# USB_OTG_HS.net
KiCad netlist of a schematic drawn in Altium Designer
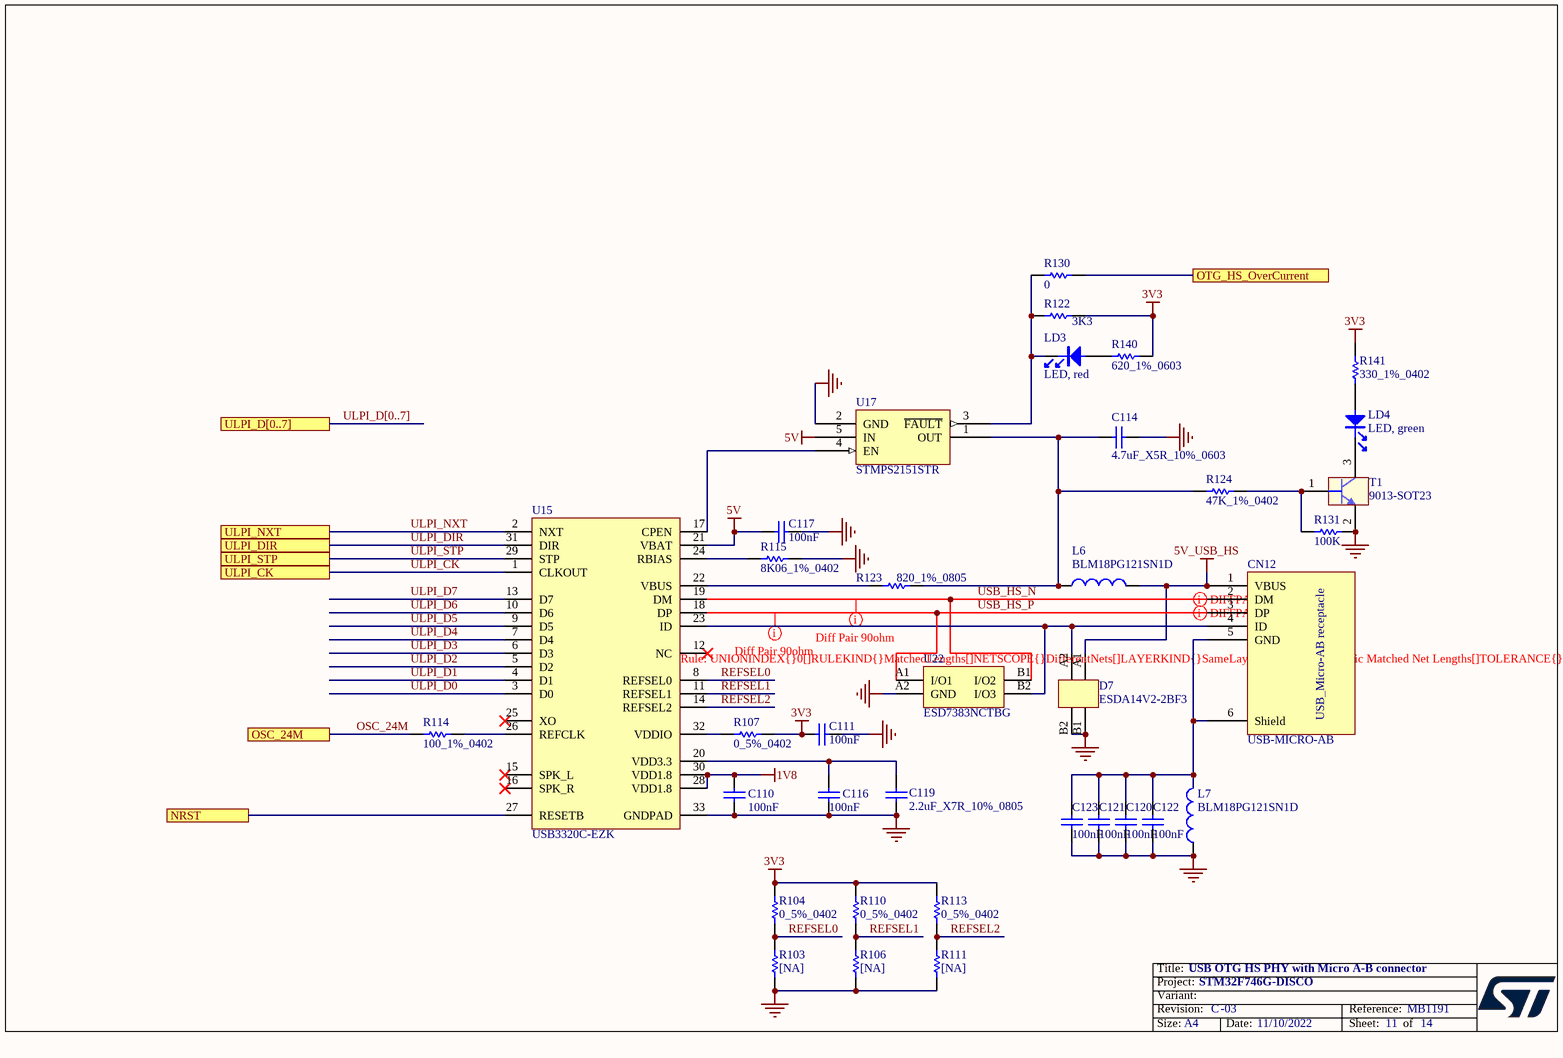
[diagram p0: USB_OTG_HS.SchDoc]

(export (version "E")
  (design (tool "Eeschema 10.0.6"))
  (components
    (comp (ref "C110")
      (value "100nF")
      (footprint "0402C")
      (description "Capacitor,100nF,16V,X7R,10%,0402,YAGEO")
      (libsource (lib "MCD_TOOLS") (part "Cap_100nF_X7R_10%_0402"))
    )
    (comp (ref "C111")
      (value "100nF")
      (footprint "0402C")
      (description "Capacitor,100nF,16V,X7R,10%,0402,YAGEO")
      (libsource (lib "MCD_TOOLS") (part "Cap_100nF_X7R_10%_0402"))
    )
    (comp (ref "C114")
      (value "4.7uF_X5R_10%_0603")
      (footprint "0603C")
      (description "Capacitor,4.7uF,16V, X5R,10%,0603,YAGEO")
      (libsource (lib "MCD_TOOLS") (part "Cap_4.7uF_X5R_10%_0603"))
    )
    (comp (ref "C116")
      (value "100nF")
      (footprint "0402C")
      (description "Capacitor,100nF,16V,X7R,10%,0402,YAGEO")
      (libsource (lib "MCD_TOOLS") (part "Cap_100nF_X7R_10%_0402"))
    )
    (comp (ref "C117")
      (value "100nF")
      (footprint "0402C")
      (description "Capacitor,100nF,16V,X7R,10%,0402,YAGEO")
      (libsource (lib "MCD_TOOLS") (part "Cap_100nF_X7R_10%_0402"))
    )
    (comp (ref "C119")
      (value "2.2uF_X7R_10%_0805")
      (footprint "0805C")
      (description "Capacitor,2.2uF,16V, X7R,10%,0805,YAGEO")
      (libsource (lib "MCD_TOOLS") (part "Cap_2.2uF_X7R_10%_0805"))
    )
    (comp (ref "C120")
      (value "100nF")
      (footprint "0402C")
      (description "Capacitor,100nF,16V,X7R,10%,0402,YAGEO")
      (libsource (lib "MCD_TOOLS") (part "Cap_100nF_X7R_10%_0402"))
    )
    (comp (ref "C121")
      (value "100nF")
      (footprint "0402C")
      (description "Capacitor,100nF,16V,X7R,10%,0402,YAGEO")
      (libsource (lib "MCD_TOOLS") (part "Cap_100nF_X7R_10%_0402"))
    )
    (comp (ref "C122")
      (value "100nF")
      (footprint "0402C")
      (description "Capacitor,100nF,16V,X7R,10%,0402,YAGEO")
      (libsource (lib "MCD_TOOLS") (part "Cap_100nF_X7R_10%_0402"))
    )
    (comp (ref "C123")
      (value "100nF")
      (footprint "0402C")
      (description "Capacitor,100nF,16V,X7R,10%,0402,YAGEO")
      (libsource (lib "MCD_TOOLS") (part "Cap_100nF_X7R_10%_0402"))
    )
    (comp (ref "CN12")
      (value "USB-MICRO-AB")
      (footprint "USB-MICRO-AB")
      (description "USB-MICRO-AB, 47590-0001, SMT, MOLEX")
      (libsource (lib "MCD_TOOLS") (part "USB-MICRO-AB"))
    )
    (comp (ref "D7")
      (value "ESDA14V2-2BF3")
      (footprint "BGA4_1X1")
      (description "Quad bidirectional Transil array for ESD protection")
      (libsource (lib "MCD_TOOLS") (part "ESDA14V2-2BF3"))
    )
    (comp (ref "L6")
      (value "BLM18PG121SN1D")
      (footprint "0603L")
      (description "Bead,120R,2A,0603,BLM18PG121SN1D,MURATA")
      (libsource (lib "MCD_TOOLS") (part "BEAD_120R_2A_0603"))
    )
    (comp (ref "L7")
      (value "BLM18PG121SN1D")
      (footprint "0603L")
      (description "Bead,120R,2A,0603,BLM18PG121SN1D,MURATA")
      (libsource (lib "MCD_TOOLS") (part "BEAD_120R_2A_0603"))
    )
    (comp (ref "LD3")
      (value "LED, red")
      (footprint "0603D")
      (description "LED, red, 0603")
      (libsource (lib "MCD_TOOLS") (part "LED_red"))
    )
    (comp (ref "LD4")
      (value "LED, green")
      (footprint "0603D")
      (description "LED, green, 0603")
      (libsource (lib "MCD_TOOLS") (part "LED_green"))
    )
    (comp (ref "R103")
      (value "[NA]")
      (footprint "0402R")
      (description "Resistor,[NA],0402")
      (libsource (lib "MCD_TOOLS") (part "Res_NA_0402"))
    )
    (comp (ref "R104")
      (value "0_5%_0402")
      (footprint "0402R")
      (description "Resistor,0,0402,5%,YAGEO")
      (libsource (lib "MCD_TOOLS") (part "Res_0_5%_0402"))
    )
    (comp (ref "R106")
      (value "[NA]")
      (footprint "0402R")
      (description "Resistor,[NA],0402")
      (libsource (lib "MCD_TOOLS") (part "Res_NA_0402"))
    )
    (comp (ref "R107")
      (value "0_5%_0402")
      (footprint "0402R")
      (description "Resistor,0,0402,5%,YAGEO")
      (libsource (lib "MCD_TOOLS") (part "Res_0_5%_0402"))
    )
    (comp (ref "R110")
      (value "0_5%_0402")
      (footprint "0402R")
      (description "Resistor,0,0402,5%,YAGEO")
      (libsource (lib "MCD_TOOLS") (part "Res_0_5%_0402"))
    )
    (comp (ref "R111")
      (value "[NA]")
      (footprint "0402R")
      (description "Resistor,[NA],0402")
      (libsource (lib "MCD_TOOLS") (part "Res_NA_0402"))
    )
    (comp (ref "R113")
      (value "0_5%_0402")
      (footprint "0402R")
      (description "Resistor,0,0402,5%,YAGEO")
      (libsource (lib "MCD_TOOLS") (part "Res_0_5%_0402"))
    )
    (comp (ref "R114")
      (value "100_1%_0402")
      (footprint "0402R")
      (description "Resistor,100,0402,1%,YAGEO")
      (libsource (lib "MCD_TOOLS") (part "Res_100_1%_0402"))
    )
    (comp (ref "R115")
      (value "8K06_1%_0402")
      (footprint "0402R")
      (description "Resistor,8K06,0402,1%,YAGEO")
      (libsource (lib "MCD_TOOLS") (part "Res_8K06_1%_0402"))
    )
    (comp (ref "R122")
      (value "3K3")
      (footprint "0402R")
      (description "Resistor,3K3,0402,1%,YAGEO")
      (libsource (lib "MCD_TOOLS") (part "Res_3K3_1%_0402"))
    )
    (comp (ref "R123")
      (value "820_1%_0805")
      (footprint "0805R")
      (description "Resistor,820,0805,1%,YAGEO")
      (libsource (lib "MCD_TOOLS") (part "Res_820_1%_0805"))
    )
    (comp (ref "R124")
      (value "47K_1%_0402")
      (footprint "0402R")
      (description "Resistor,47K,0402,1%,YAGEO")
      (libsource (lib "MCD_TOOLS") (part "Res_47K_1%_0402"))
    )
    (comp (ref "R130")
      (value "0")
      (footprint "0402R")
      (description "Resistor,0,0402,5%,YAGEO")
      (libsource (lib "MCD_TOOLS") (part "Res_0_5%_0402"))
    )
    (comp (ref "R131")
      (value "100K")
      (footprint "0402R")
      (description "Resistor,100K,0402,1%,YAGEO")
      (libsource (lib "MCD_TOOLS") (part "Res_100K_1%_0402"))
    )
    (comp (ref "R140")
      (value "620_1%_0603")
      (footprint "0603R")
      (description "Resistor,620,0603,1%,VISHAY")
      (libsource (lib "MCD_TOOLS") (part "Res_620_1%_0603"))
    )
    (comp (ref "R141")
      (value "330_1%_0402")
      (footprint "0402R")
      (description "Resistor,330,0402,1%,YAGEO")
      (libsource (lib "MCD_TOOLS") (part "Res_330_1%_0402"))
    )
    (comp (ref "T1")
      (value "9013-SOT23")
      (footprint "SOT23")
      (description "NPN Bipolar Transistor")
      (libsource (lib "MCD_TOOLS") (part "9013-SOT23"))
    )
    (comp (ref "U15")
      (value "USB3320C-EZK")
      (footprint "QFN32_0R5_5X5")
      (description "USB3320C,  Hi-Speed USB Host, Device or OTG PHY with ULPI Low Pin Interface")
      (libsource (lib "MCD_TOOLS") (part "USB3320C-EZK"))
    )
    (comp (ref "U17")
      (value "STMPS2151STR")
      (footprint "SOT23-5L")
      (description "Enhanced single channel power switches")
      (libsource (lib "MCD_TOOLS") (part "STMPS2151STR"))
    )
    (comp (ref "U22")
      (value "ESD7383NCTBG")
      (footprint "ESD_WLCSP4_CASE-567CB_0P80X0P80_P040")
      (description "3-line low capacitance protection for high speed USB")
      (fields (field (name "PROVIDED") "SUBCO"))
      (libsource (lib "Mb1191") (part "ESD7383NCTBG"))
    )
  )
  (nets
    (net (code "1") (name "/NRST") (class "Default")
      (node (ref "U15") (pin "27") (pinfunction "RESETB_27") (pintype "passive"))
    )
    (net (code "2") (name "/OSC_24M") (class "Default")
      (node (ref "R114") (pin "1") (pinfunction "1_1") (pintype "passive"))
    )
    (net (code "3") (name "/OTG_HS_OverCurrent") (class "Default")
      (node (ref "R130") (pin "2") (pinfunction "2_2") (pintype "passive"))
    )
    (net (code "4") (name "/REFSEL0") (class "Default")
      (node (ref "R103") (pin "2") (pinfunction "2_2") (pintype "passive"))
      (node (ref "R104") (pin "1") (pinfunction "1_1") (pintype "passive"))
      (node (ref "U15") (pin "8") (pinfunction "REFSEL0_8") (pintype "passive"))
    )
    (net (code "5") (name "/REFSEL1") (class "Default")
      (node (ref "R106") (pin "2") (pinfunction "2_2") (pintype "passive"))
      (node (ref "R110") (pin "1") (pinfunction "1_1") (pintype "passive"))
      (node (ref "U15") (pin "11") (pinfunction "REFSEL1_11") (pintype "passive"))
    )
    (net (code "6") (name "/REFSEL2") (class "Default")
      (node (ref "R111") (pin "2") (pinfunction "2_2") (pintype "passive"))
      (node (ref "R113") (pin "1") (pinfunction "1_1") (pintype "passive"))
      (node (ref "U15") (pin "14") (pinfunction "REFSEL2_14") (pintype "passive"))
    )
    (net (code "7") (name "/ULPI_CK") (class "Default")
      (node (ref "U15") (pin "1") (pinfunction "CLKOUT_1") (pintype "passive"))
    )
    (net (code "8") (name "/ULPI_D0") (class "Default")
      (node (ref "U15") (pin "3") (pinfunction "D0_3") (pintype "passive"))
    )
    (net (code "9") (name "/ULPI_D1") (class "Default")
      (node (ref "U15") (pin "4") (pinfunction "D1_4") (pintype "passive"))
    )
    (net (code "10") (name "/ULPI_D2") (class "Default")
      (node (ref "U15") (pin "5") (pinfunction "D2_5") (pintype "passive"))
    )
    (net (code "11") (name "/ULPI_D3") (class "Default")
      (node (ref "U15") (pin "6") (pinfunction "D3_6") (pintype "passive"))
    )
    (net (code "12") (name "/ULPI_D4") (class "Default")
      (node (ref "U15") (pin "7") (pinfunction "D4_7") (pintype "passive"))
    )
    (net (code "13") (name "/ULPI_D5") (class "Default")
      (node (ref "U15") (pin "9") (pinfunction "D5_9") (pintype "passive"))
    )
    (net (code "14") (name "/ULPI_D6") (class "Default")
      (node (ref "U15") (pin "10") (pinfunction "D6_10") (pintype "passive"))
    )
    (net (code "15") (name "/ULPI_D7") (class "Default")
      (node (ref "U15") (pin "13") (pinfunction "D7_13") (pintype "passive"))
    )
    (net (code "16") (name "/ULPI_DIR") (class "Default")
      (node (ref "U15") (pin "31") (pinfunction "DIR_31") (pintype "passive"))
    )
    (net (code "18") (name "/ULPI_NXT") (class "Default")
      (node (ref "U15") (pin "2") (pinfunction "NXT_2") (pintype "passive"))
    )
    (net (code "19") (name "/ULPI_STP") (class "Default")
      (node (ref "U15") (pin "29") (pinfunction "STP_29") (pintype "passive"))
    )
    (net (code "20") (name "/USB_HS_N") (class "Default")
      (node (ref "CN12") (pin "2") (pinfunction "DM_2") (pintype "passive"))
      (node (ref "U15") (pin "19") (pinfunction "DM_19") (pintype "passive"))
      (node (ref "U22") (pin "B1") (pinfunction "I/O2_B1") (pintype "passive"))
    )
    (net (code "21") (name "/USB_HS_P") (class "Default")
      (node (ref "CN12") (pin "3") (pinfunction "DP_3") (pintype "passive"))
      (node (ref "U15") (pin "18") (pinfunction "DP_18") (pintype "passive"))
      (node (ref "U22") (pin "A1") (pinfunction "I/O1_A1") (pintype "passive"))
    )
    (net (code "22") (name "1V8") (class "Default")
      (node (ref "C110") (pin "2") (pinfunction "2_2") (pintype "passive"))
      (node (ref "U15") (pin "28") (pinfunction "VDD1.8_28") (pintype "passive"))
      (node (ref "U15") (pin "30") (pinfunction "VDD1.8_30") (pintype "passive"))
    )
    (net (code "23") (name "3V3") (class "Default")
      (node (ref "C111") (pin "1") (pinfunction "1_1") (pintype "passive"))
      (node (ref "R104") (pin "2") (pinfunction "2_2") (pintype "passive"))
      (node (ref "R107") (pin "2") (pinfunction "2_2") (pintype "passive"))
      (node (ref "R110") (pin "2") (pinfunction "2_2") (pintype "passive"))
      (node (ref "R113") (pin "2") (pinfunction "2_2") (pintype "passive"))
      (node (ref "R122") (pin "1") (pinfunction "1_1") (pintype "passive"))
      (node (ref "R140") (pin "2") (pinfunction "2_2") (pintype "passive"))
      (node (ref "R141") (pin "2") (pinfunction "2_2") (pintype "passive"))
    )
    (net (code "24") (name "5V") (class "Default")
      (node (ref "C117") (pin "1") (pinfunction "1_1") (pintype "passive"))
      (node (ref "U15") (pin "21") (pinfunction "VBAT_21") (pintype "passive"))
      (node (ref "U17") (pin "5") (pinfunction "IN_5") (pintype "passive"))
    )
    (net (code "25") (name "5V_USB_HS") (class "Default")
      (node (ref "CN12") (pin "1") (pinfunction "VBUS_1") (pintype "passive"))
      (node (ref "D7") (pin "A1") (pintype "passive"))
      (node (ref "L6") (pin "2") (pinfunction "2_2") (pintype "passive"))
    )
    (net (code "26") (name "GND") (class "Default")
      (node (ref "C110") (pin "1") (pinfunction "1_1") (pintype "passive"))
      (node (ref "C111") (pin "2") (pinfunction "2_2") (pintype "passive"))
      (node (ref "C114") (pin "2") (pinfunction "2_2") (pintype "passive"))
      (node (ref "C116") (pin "1") (pinfunction "1_1") (pintype "passive"))
      (node (ref "C117") (pin "2") (pinfunction "2_2") (pintype "passive"))
      (node (ref "C119") (pin "1") (pinfunction "1_1") (pintype "passive"))
      (node (ref "C120") (pin "1") (pinfunction "1_1") (pintype "passive"))
      (node (ref "C121") (pin "1") (pinfunction "1_1") (pintype "passive"))
      (node (ref "C122") (pin "1") (pinfunction "1_1") (pintype "passive"))
      (node (ref "C123") (pin "1") (pinfunction "1_1") (pintype "passive"))
      (node (ref "D7") (pin "B1") (pintype "passive"))
      (node (ref "D7") (pin "B2") (pintype "passive"))
      (node (ref "L7") (pin "1") (pinfunction "1_1") (pintype "passive"))
      (node (ref "R103") (pin "1") (pinfunction "1_1") (pintype "passive"))
      (node (ref "R106") (pin "1") (pinfunction "1_1") (pintype "passive"))
      (node (ref "R111") (pin "1") (pinfunction "1_1") (pintype "passive"))
      (node (ref "R115") (pin "2") (pinfunction "2_2") (pintype "passive"))
      (node (ref "R131") (pin "2") (pinfunction "2_2") (pintype "passive"))
      (node (ref "T1") (pin "2") (pinfunction "E_2") (pintype "passive"))
      (node (ref "U15") (pin "33") (pinfunction "GNDPAD_33") (pintype "passive"))
      (node (ref "U17") (pin "2") (pinfunction "GND_2") (pintype "passive"))
      (node (ref "U22") (pin "A2") (pinfunction "GND_A2") (pintype "passive"))
    )
    (net (code "27") (name "Net-(CN12-GND)") (class "Default")
      (node (ref "C120") (pin "2") (pinfunction "2_2") (pintype "passive"))
      (node (ref "C121") (pin "2") (pinfunction "2_2") (pintype "passive"))
      (node (ref "C122") (pin "2") (pinfunction "2_2") (pintype "passive"))
      (node (ref "C123") (pin "2") (pinfunction "2_2") (pintype "passive"))
      (node (ref "CN12") (pin "5") (pinfunction "GND_5") (pintype "passive"))
      (node (ref "CN12") (pin "6") (pinfunction "Shield_6") (pintype "passive"))
      (node (ref "L7") (pin "2") (pinfunction "2_2") (pintype "passive"))
    )
    (net (code "28") (name "Net-(CN12-ID)") (class "Default")
      (node (ref "CN12") (pin "4") (pinfunction "ID_4") (pintype "passive"))
      (node (ref "D7") (pin "A2") (pintype "passive"))
      (node (ref "U15") (pin "23") (pinfunction "ID_23") (pintype "passive"))
      (node (ref "U22") (pin "B2") (pinfunction "I/O3_B2") (pintype "passive"))
    )
    (net (code "29") (name "Net-(LD3-Pad1)") (class "Default")
      (node (ref "LD3") (pin "1") (pintype "passive"))
      (node (ref "R140") (pin "1") (pinfunction "1_1") (pintype "passive"))
    )
    (net (code "30") (name "Net-(LD4-Pad1)") (class "Default")
      (node (ref "LD4") (pin "1") (pintype "passive"))
      (node (ref "R141") (pin "1") (pinfunction "1_1") (pintype "passive"))
    )
    (net (code "31") (name "Net-(T1-B)") (class "Default")
      (node (ref "R124") (pin "2") (pinfunction "2_2") (pintype "passive"))
      (node (ref "R131") (pin "1") (pinfunction "1_1") (pintype "passive"))
      (node (ref "T1") (pin "1") (pinfunction "B_1") (pintype "passive"))
    )
    (net (code "32") (name "Net-(T1-C)") (class "Default")
      (node (ref "LD4") (pin "2") (pintype "passive"))
      (node (ref "T1") (pin "3") (pinfunction "C_3") (pintype "passive"))
    )
    (net (code "33") (name "Net-(U15-CPEN)") (class "Default")
      (node (ref "U15") (pin "17") (pinfunction "CPEN_17") (pintype "passive"))
      (node (ref "U17") (pin "4") (pinfunction "EN_4") (pintype "input"))
    )
    (net (code "34") (name "Net-(U15-RBIAS)") (class "Default")
      (node (ref "R115") (pin "1") (pinfunction "1_1") (pintype "passive"))
      (node (ref "U15") (pin "24") (pinfunction "RBIAS_24") (pintype "passive"))
    )
    (net (code "35") (name "Net-(U15-REFCLK)") (class "Default")
      (node (ref "R114") (pin "2") (pinfunction "2_2") (pintype "passive"))
      (node (ref "U15") (pin "26") (pinfunction "REFCLK_26") (pintype "passive"))
    )
    (net (code "36") (name "Net-(U15-VBUS)") (class "Default")
      (node (ref "R123") (pin "1") (pinfunction "1_1") (pintype "passive"))
      (node (ref "U15") (pin "22") (pinfunction "VBUS_22") (pintype "passive"))
    )
    (net (code "37") (name "Net-(U15-VDD3.3)") (class "Default")
      (node (ref "C116") (pin "2") (pinfunction "2_2") (pintype "passive"))
      (node (ref "C119") (pin "2") (pinfunction "2_2") (pintype "passive"))
      (node (ref "U15") (pin "20") (pinfunction "VDD3.3_20") (pintype "passive"))
    )
    (net (code "38") (name "Net-(U15-VDDIO)") (class "Default")
      (node (ref "R107") (pin "1") (pinfunction "1_1") (pintype "passive"))
      (node (ref "U15") (pin "32") (pinfunction "VDDIO_32") (pintype "passive"))
    )
    (net (code "39") (name "Net-(U17-OUT)") (class "Default")
      (node (ref "C114") (pin "1") (pinfunction "1_1") (pintype "passive"))
      (node (ref "L6") (pin "1") (pinfunction "1_1") (pintype "passive"))
      (node (ref "R123") (pin "2") (pinfunction "2_2") (pintype "passive"))
      (node (ref "R124") (pin "1") (pinfunction "1_1") (pintype "passive"))
      (node (ref "U17") (pin "1") (pinfunction "OUT_1") (pintype "passive"))
    )
    (net (code "40") (name "Net-(U17-~{FAULT})") (class "Default")
      (node (ref "LD3") (pin "2") (pintype "passive"))
      (node (ref "R122") (pin "2") (pinfunction "2_2") (pintype "passive"))
      (node (ref "R130") (pin "1") (pinfunction "1_1") (pintype "passive"))
      (node (ref "U17") (pin "3") (pinfunction "~{FAULT}_3") (pintype "output"))
    )
    (net (code "41") (name "unconnected-(U15-NC-Pad12)") (class "Default")
      (node (ref "U15") (pin "12") (pinfunction "NC_12") (pintype "passive+no_connect"))
    )
    (net (code "42") (name "unconnected-(U15-SPK_L-Pad15)") (class "Default")
      (node (ref "U15") (pin "15") (pinfunction "SPK_L_15") (pintype "passive+no_connect"))
    )
    (net (code "43") (name "unconnected-(U15-SPK_R-Pad16)") (class "Default")
      (node (ref "U15") (pin "16") (pinfunction "SPK_R_16") (pintype "passive+no_connect"))
    )
    (net (code "44") (name "unconnected-(U15-XO-Pad25)") (class "Default")
      (node (ref "U15") (pin "25") (pinfunction "XO_25") (pintype "passive+no_connect"))
    )
  )
)
